# UART.net
KiCad netlist of a schematic drawn in Altium Designer
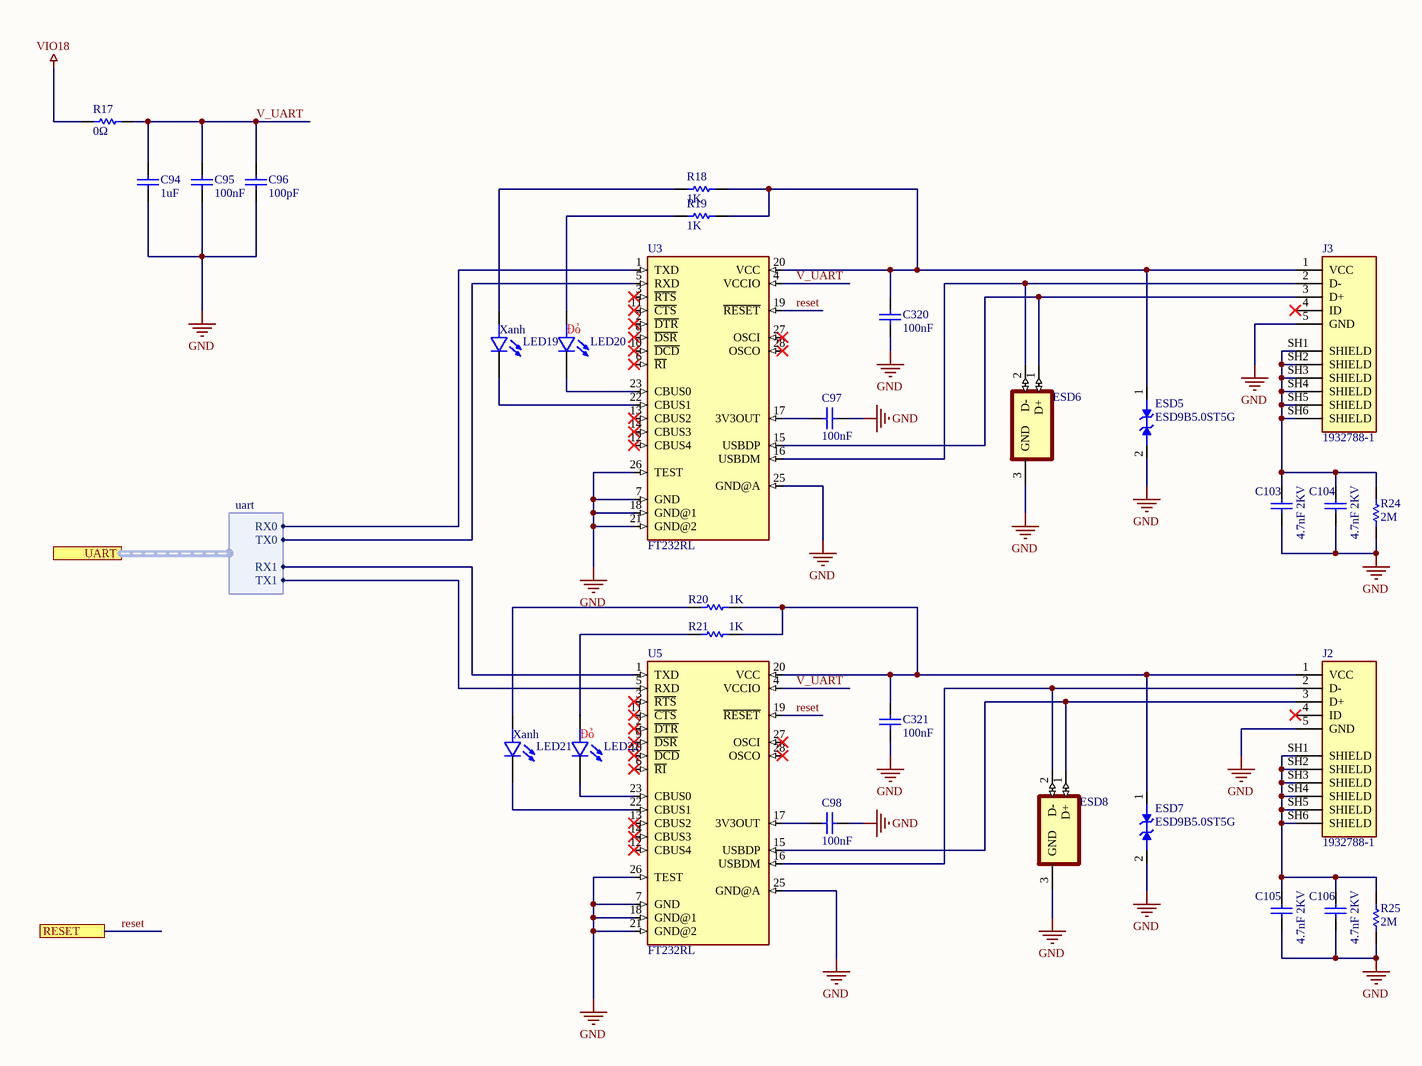
[diagram p0: UART.SchDoc]

(export (version "E")
  (design (tool "Eeschema 10.0.6"))
  (components
    (comp (ref "C94")
      (value "1uF")
      (footprint "C0805")
      (fields (field (name "Comment") "C0805"))
      (libsource (lib "kit") (part "C0805"))
    )
    (comp (ref "C95")
      (value "100nF")
      (footprint "C0603")
      (fields (field (name "Comment") "C0603"))
      (libsource (lib "kit") (part "C0603"))
    )
    (comp (ref "C96")
      (value "100pF")
      (footprint "C0402")
      (fields (field (name "Comment") "C0402"))
      (libsource (lib "kit") (part "C0402"))
    )
    (comp (ref "C97")
      (value "100nF")
      (footprint "C0603")
      (fields (field (name "Comment") "C0603"))
      (libsource (lib "kit") (part "C0603"))
    )
    (comp (ref "C98")
      (value "100nF")
      (footprint "C0603")
      (fields (field (name "Comment") "C0603"))
      (libsource (lib "kit") (part "C0603"))
    )
    (comp (ref "C103")
      (value "4.7nF 2KV")
      (footprint "C1210")
      (fields (field (name "Comment") "C1210"))
      (libsource (lib "kit") (part "C1210"))
    )
    (comp (ref "C104")
      (value "4.7nF 2KV")
      (footprint "C1210")
      (fields (field (name "Comment") "C1210"))
      (libsource (lib "kit") (part "C1210"))
    )
    (comp (ref "C105")
      (value "4.7nF 2KV")
      (footprint "C1210")
      (fields (field (name "Comment") "C1210"))
      (libsource (lib "kit") (part "C1210"))
    )
    (comp (ref "C106")
      (value "4.7nF 2KV")
      (footprint "C1210")
      (fields (field (name "Comment") "C1210"))
      (libsource (lib "kit") (part "C1210"))
    )
    (comp (ref "C320")
      (value "100nF")
      (footprint "C0603")
      (fields (field (name "Comment") "C0603"))
      (libsource (lib "kit") (part "C0603"))
    )
    (comp (ref "C321")
      (value "100nF")
      (footprint "C0603")
      (fields (field (name "Comment") "C0603"))
      (libsource (lib "kit") (part "C0603"))
    )
    (comp (ref "ESD5")
      (value "ESD9B5.0ST5G")
      (footprint "SODFL1006X40N")
      (description "Clamp Ipp Tvs Diode Surface Mount SOD-923")
      (libsource (lib "kit") (part "ESD9B5.0ST5G"))
    )
    (comp (ref "ESD6")
      (value "TPD2EUSB30DRTR")
      (footprint "SOTFL35P100X50-3N")
      (description "2-channel ESD solution for SuperSpeed USB 3.0 interface 3-SOT-9X3 -40 to 85")
      (libsource (lib "kit") (part "TPD2EUSB30DRTR"))
    )
    (comp (ref "ESD7")
      (value "ESD9B5.0ST5G")
      (footprint "SODFL1006X40N")
      (description "Clamp Ipp Tvs Diode Surface Mount SOD-923")
      (libsource (lib "kit") (part "ESD9B5.0ST5G"))
    )
    (comp (ref "ESD8")
      (value "TPD2EUSB30DRTR")
      (footprint "SOTFL35P100X50-3N")
      (description "2-channel ESD solution for SuperSpeed USB 3.0 interface 3-SOT-9X3 -40 to 85")
      (libsource (lib "kit") (part "TPD2EUSB30DRTR"))
    )
    (comp (ref "J2")
      (value "1932788-1")
      (footprint "TE_1932788-1")
      (libsource (lib "kit") (part "1932788-1"))
    )
    (comp (ref "J3")
      (value "1932788-1")
      (footprint "TE_1932788-1")
      (libsource (lib "kit") (part "1932788-1"))
    )
    (comp (ref "LED19")
      (value "LED0402")
      (footprint "LED0402")
      (description "LED SMD")
      (libsource (lib "kit") (part "LED0402"))
    )
    (comp (ref "LED20")
      (value "LED0402")
      (footprint "LED0402")
      (description "LED SMD")
      (libsource (lib "kit") (part "LED0402"))
    )
    (comp (ref "LED21")
      (value "LED0402")
      (footprint "LED0402")
      (description "LED SMD")
      (libsource (lib "kit") (part "LED0402"))
    )
    (comp (ref "LED22")
      (value "LED0402")
      (footprint "LED0402")
      (description "LED SMD")
      (libsource (lib "kit") (part "LED0402"))
    )
    (comp (ref "R17")
      (value "0Ω")
      (footprint "R0603")
      (fields (field (name "Comment") "R0603"))
      (libsource (lib "kit") (part "R0603"))
    )
    (comp (ref "R18")
      (value "1K")
      (footprint "R0603")
      (fields (field (name "Comment") "R0603"))
      (libsource (lib "kit") (part "R0603"))
    )
    (comp (ref "R19")
      (value "1K")
      (footprint "R0603")
      (fields (field (name "Comment") "R0603"))
      (libsource (lib "kit") (part "R0603"))
    )
    (comp (ref "R20")
      (value "1K")
      (footprint "R0603")
      (fields (field (name "Comment") "R0603"))
      (libsource (lib "kit") (part "R0603"))
    )
    (comp (ref "R21")
      (value "1K")
      (footprint "R0603")
      (fields (field (name "Comment") "R0603"))
      (libsource (lib "kit") (part "R0603"))
    )
    (comp (ref "R24")
      (value "2M")
      (footprint "R0603")
      (fields (field (name "Comment") "R0603"))
      (libsource (lib "kit") (part "R0603"))
    )
    (comp (ref "R25")
      (value "2M")
      (footprint "R0603")
      (fields (field (name "Comment") "R0603"))
      (libsource (lib "kit") (part "R0603"))
    )
    (comp (ref "U3") (value "FT232RL") (footprint "FT232RL") (libsource (lib "kit") (part "FT232RL")))
    (comp (ref "U5") (value "FT232RL") (footprint "FT232RL") (libsource (lib "kit") (part "FT232RL")))
  )
  (nets
    (net (code "2") (name "/RX0") (class "Default")
      (node (ref "U3") (pin "1") (pinfunction "TXD_1") (pintype "input"))
    )
    (net (code "3") (name "/RX1") (class "Default")
      (node (ref "U5") (pin "1") (pinfunction "TXD_1") (pintype "input"))
    )
    (net (code "4") (name "/TX0") (class "Default")
      (node (ref "U3") (pin "5") (pinfunction "RXD_5") (pintype "input"))
    )
    (net (code "5") (name "/TX1") (class "Default")
      (node (ref "U5") (pin "5") (pinfunction "RXD_5") (pintype "input"))
    )
    (net (code "6") (name "/V_UART") (class "Default")
      (node (ref "C94") (pin "1") (pinfunction "1_1") (pintype "passive"))
      (node (ref "C95") (pin "2") (pinfunction "2_2") (pintype "passive"))
      (node (ref "C96") (pin "2") (pinfunction "2_2") (pintype "passive"))
      (node (ref "R17") (pin "2") (pinfunction "2_2") (pintype "passive"))
      (node (ref "U3") (pin "4") (pinfunction "VCCIO_4") (pintype "input"))
      (node (ref "U5") (pin "4") (pinfunction "VCCIO_4") (pintype "input"))
    )
    (net (code "7") (name "/reset") (class "Default")
      (node (ref "U3") (pin "19") (pinfunction "~{RESET}_19") (pintype "input"))
      (node (ref "U5") (pin "19") (pinfunction "~{RESET}_19") (pintype "input"))
    )
    (net (code "9") (name "GND") (class "Default")
      (node (ref "C103") (pin "1") (pinfunction "1_1") (pintype "passive"))
      (node (ref "C104") (pin "1") (pinfunction "1_1") (pintype "passive"))
      (node (ref "C105") (pin "1") (pinfunction "1_1") (pintype "passive"))
      (node (ref "C106") (pin "1") (pinfunction "1_1") (pintype "passive"))
      (node (ref "C320") (pin "1") (pinfunction "1_1") (pintype "passive"))
      (node (ref "C321") (pin "1") (pinfunction "1_1") (pintype "passive"))
      (node (ref "C94") (pin "2") (pinfunction "2_2") (pintype "passive"))
      (node (ref "C95") (pin "1") (pinfunction "1_1") (pintype "passive"))
      (node (ref "C96") (pin "1") (pinfunction "1_1") (pintype "passive"))
      (node (ref "C97") (pin "1") (pinfunction "1_1") (pintype "passive"))
      (node (ref "C98") (pin "1") (pinfunction "1_1") (pintype "passive"))
      (node (ref "ESD5") (pin "2") (pinfunction "A1_2") (pintype "passive"))
      (node (ref "ESD6") (pin "3") (pinfunction "GND_3") (pintype "power_in"))
      (node (ref "ESD7") (pin "2") (pinfunction "A1_2") (pintype "passive"))
      (node (ref "ESD8") (pin "3") (pinfunction "GND_3") (pintype "power_in"))
      (node (ref "J2") (pin "5") (pinfunction "GND_5") (pintype "power_in"))
      (node (ref "J3") (pin "5") (pinfunction "GND_5") (pintype "power_in"))
      (node (ref "R24") (pin "2") (pinfunction "2_2") (pintype "passive"))
      (node (ref "R25") (pin "2") (pinfunction "2_2") (pintype "passive"))
      (node (ref "U3") (pin "18") (pinfunction "GND@1_18") (pintype "input"))
      (node (ref "U3") (pin "21") (pinfunction "GND@2_21") (pintype "input"))
      (node (ref "U3") (pin "25") (pinfunction "GND@A_25") (pintype "input"))
      (node (ref "U3") (pin "26") (pinfunction "TEST_26") (pintype "input"))
      (node (ref "U3") (pin "7") (pinfunction "GND_7") (pintype "input"))
      (node (ref "U5") (pin "18") (pinfunction "GND@1_18") (pintype "input"))
      (node (ref "U5") (pin "21") (pinfunction "GND@2_21") (pintype "input"))
      (node (ref "U5") (pin "25") (pinfunction "GND@A_25") (pintype "input"))
      (node (ref "U5") (pin "26") (pinfunction "TEST_26") (pintype "input"))
      (node (ref "U5") (pin "7") (pinfunction "GND_7") (pintype "input"))
    )
    (net (code "10") (name "Net-(C103-Pad2)") (class "Default")
      (node (ref "C103") (pin "2") (pinfunction "2_2") (pintype "passive"))
      (node (ref "C104") (pin "2") (pinfunction "2_2") (pintype "passive"))
      (node (ref "J3") (pin "SH1") (pinfunction "SHIELD_SH1") (pintype "passive"))
      (node (ref "J3") (pin "SH2") (pinfunction "SHIELD_SH2") (pintype "passive"))
      (node (ref "J3") (pin "SH3") (pinfunction "SHIELD_SH3") (pintype "passive"))
      (node (ref "J3") (pin "SH4") (pinfunction "SHIELD_SH4") (pintype "passive"))
      (node (ref "J3") (pin "SH5") (pinfunction "SHIELD_SH5") (pintype "passive"))
      (node (ref "J3") (pin "SH6") (pinfunction "SHIELD_SH6") (pintype "passive"))
      (node (ref "R24") (pin "1") (pinfunction "1_1") (pintype "passive"))
    )
    (net (code "11") (name "Net-(C105-Pad2)") (class "Default")
      (node (ref "C105") (pin "2") (pinfunction "2_2") (pintype "passive"))
      (node (ref "C106") (pin "2") (pinfunction "2_2") (pintype "passive"))
      (node (ref "J2") (pin "SH1") (pinfunction "SHIELD_SH1") (pintype "passive"))
      (node (ref "J2") (pin "SH2") (pinfunction "SHIELD_SH2") (pintype "passive"))
      (node (ref "J2") (pin "SH3") (pinfunction "SHIELD_SH3") (pintype "passive"))
      (node (ref "J2") (pin "SH4") (pinfunction "SHIELD_SH4") (pintype "passive"))
      (node (ref "J2") (pin "SH5") (pinfunction "SHIELD_SH5") (pintype "passive"))
      (node (ref "J2") (pin "SH6") (pinfunction "SHIELD_SH6") (pintype "passive"))
      (node (ref "R25") (pin "1") (pinfunction "1_1") (pintype "passive"))
    )
    (net (code "12") (name "Net-(ESD5-A)") (class "Default")
      (node (ref "C320") (pin "2") (pinfunction "2_2") (pintype "passive"))
      (node (ref "ESD5") (pin "1") (pinfunction "A_1") (pintype "passive"))
      (node (ref "J3") (pin "1") (pinfunction "VCC_1") (pintype "power_in"))
      (node (ref "R18") (pin "2") (pinfunction "2_2") (pintype "passive"))
      (node (ref "R19") (pin "2") (pinfunction "2_2") (pintype "passive"))
      (node (ref "U3") (pin "20") (pinfunction "VCC_20") (pintype "input"))
    )
    (net (code "13") (name "Net-(ESD6-D+)") (class "Default")
      (node (ref "ESD6") (pin "1") (pinfunction "D+_1") (pintype "bidirectional"))
      (node (ref "J3") (pin "3") (pinfunction "D+_3") (pintype "passive"))
      (node (ref "U3") (pin "15") (pinfunction "USBDP_15") (pintype "input"))
    )
    (net (code "14") (name "Net-(ESD6-D-)") (class "Default")
      (node (ref "ESD6") (pin "2") (pinfunction "D-_2") (pintype "bidirectional"))
      (node (ref "J3") (pin "2") (pinfunction "D-_2") (pintype "passive"))
      (node (ref "U3") (pin "16") (pinfunction "USBDM_16") (pintype "input"))
    )
    (net (code "15") (name "Net-(ESD7-A)") (class "Default")
      (node (ref "C321") (pin "2") (pinfunction "2_2") (pintype "passive"))
      (node (ref "ESD7") (pin "1") (pinfunction "A_1") (pintype "passive"))
      (node (ref "J2") (pin "1") (pinfunction "VCC_1") (pintype "power_in"))
      (node (ref "R20") (pin "2") (pinfunction "2_2") (pintype "passive"))
      (node (ref "R21") (pin "2") (pinfunction "2_2") (pintype "passive"))
      (node (ref "U5") (pin "20") (pinfunction "VCC_20") (pintype "input"))
    )
    (net (code "16") (name "Net-(ESD8-D+)") (class "Default")
      (node (ref "ESD8") (pin "1") (pinfunction "D+_1") (pintype "bidirectional"))
      (node (ref "J2") (pin "3") (pinfunction "D+_3") (pintype "passive"))
      (node (ref "U5") (pin "15") (pinfunction "USBDP_15") (pintype "input"))
    )
    (net (code "17") (name "Net-(ESD8-D-)") (class "Default")
      (node (ref "ESD8") (pin "2") (pinfunction "D-_2") (pintype "bidirectional"))
      (node (ref "J2") (pin "2") (pinfunction "D-_2") (pintype "passive"))
      (node (ref "U5") (pin "16") (pinfunction "USBDM_16") (pintype "input"))
    )
    (net (code "18") (name "Net-(LED19-PadA)") (class "Default")
      (node (ref "LED19") (pin "A") (pinfunction "A_A") (pintype "passive"))
      (node (ref "R18") (pin "1") (pinfunction "1_1") (pintype "passive"))
    )
    (net (code "19") (name "Net-(LED20-PadA)") (class "Default")
      (node (ref "LED20") (pin "A") (pinfunction "A_A") (pintype "passive"))
      (node (ref "R19") (pin "1") (pinfunction "1_1") (pintype "passive"))
    )
    (net (code "20") (name "Net-(LED21-PadA)") (class "Default")
      (node (ref "LED21") (pin "A") (pinfunction "A_A") (pintype "passive"))
      (node (ref "R20") (pin "1") (pinfunction "1_1") (pintype "passive"))
    )
    (net (code "21") (name "Net-(LED22-PadA)") (class "Default")
      (node (ref "LED22") (pin "A") (pinfunction "A_A") (pintype "passive"))
      (node (ref "R21") (pin "1") (pinfunction "1_1") (pintype "passive"))
    )
    (net (code "22") (name "Net-(U3-3V3OUT)") (class "Default")
      (node (ref "C97") (pin "2") (pinfunction "2_2") (pintype "passive"))
      (node (ref "U3") (pin "17") (pinfunction "3V3OUT_17") (pintype "input"))
    )
    (net (code "23") (name "Net-(U3-CBUS0)") (class "Default")
      (node (ref "LED20") (pin "C") (pinfunction "C_C") (pintype "passive"))
      (node (ref "U3") (pin "23") (pinfunction "CBUS0_23") (pintype "input"))
    )
    (net (code "24") (name "Net-(U3-CBUS1)") (class "Default")
      (node (ref "LED19") (pin "C") (pinfunction "C_C") (pintype "passive"))
      (node (ref "U3") (pin "22") (pinfunction "CBUS1_22") (pintype "input"))
    )
    (net (code "25") (name "Net-(U5-3V3OUT)") (class "Default")
      (node (ref "C98") (pin "2") (pinfunction "2_2") (pintype "passive"))
      (node (ref "U5") (pin "17") (pinfunction "3V3OUT_17") (pintype "input"))
    )
    (net (code "26") (name "Net-(U5-CBUS0)") (class "Default")
      (node (ref "LED22") (pin "C") (pinfunction "C_C") (pintype "passive"))
      (node (ref "U5") (pin "23") (pinfunction "CBUS0_23") (pintype "input"))
    )
    (net (code "27") (name "Net-(U5-CBUS1)") (class "Default")
      (node (ref "LED21") (pin "C") (pinfunction "C_C") (pintype "passive"))
      (node (ref "U5") (pin "22") (pinfunction "CBUS1_22") (pintype "input"))
    )
    (net (code "28") (name "VIO18") (class "Default")
      (node (ref "R17") (pin "1") (pinfunction "1_1") (pintype "passive"))
    )
    (net (code "29") (name "unconnected-(J2-ID-Pad4)") (class "Default")
      (node (ref "J2") (pin "4") (pinfunction "ID_4") (pintype "passive+no_connect"))
    )
    (net (code "30") (name "unconnected-(J3-ID-Pad4)") (class "Default")
      (node (ref "J3") (pin "4") (pinfunction "ID_4") (pintype "passive+no_connect"))
    )
    (net (code "31") (name "unconnected-(U3-CBUS2-Pad13)") (class "Default")
      (node (ref "U3") (pin "13") (pinfunction "CBUS2_13") (pintype "input+no_connect"))
    )
    (net (code "32") (name "unconnected-(U3-CBUS3-Pad14)") (class "Default")
      (node (ref "U3") (pin "14") (pinfunction "CBUS3_14") (pintype "input+no_connect"))
    )
    (net (code "33") (name "unconnected-(U3-CBUS4-Pad12)") (class "Default")
      (node (ref "U3") (pin "12") (pinfunction "CBUS4_12") (pintype "input+no_connect"))
    )
    (net (code "34") (name "unconnected-(U3-OSCI-Pad27)") (class "Default")
      (node (ref "U3") (pin "27") (pinfunction "OSCI_27") (pintype "input+no_connect"))
    )
    (net (code "35") (name "unconnected-(U3-OSCO-Pad28)") (class "Default")
      (node (ref "U3") (pin "28") (pinfunction "OSCO_28") (pintype "input+no_connect"))
    )
    (net (code "36") (name "unconnected-(U3-~{CTS}-Pad11)") (class "Default")
      (node (ref "U3") (pin "11") (pinfunction "~{CTS}_11") (pintype "input+no_connect"))
    )
    (net (code "37") (name "unconnected-(U3-~{DCD}-Pad10)") (class "Default")
      (node (ref "U3") (pin "10") (pinfunction "~{DCD}_10") (pintype "input+no_connect"))
    )
    (net (code "38") (name "unconnected-(U3-~{DSR}-Pad9)") (class "Default")
      (node (ref "U3") (pin "9") (pinfunction "~{DSR}_9") (pintype "input+no_connect"))
    )
    (net (code "39") (name "unconnected-(U3-~{DTR}-Pad2)") (class "Default")
      (node (ref "U3") (pin "2") (pinfunction "~{DTR}_2") (pintype "input+no_connect"))
    )
    (net (code "40") (name "unconnected-(U3-~{RI}-Pad6)") (class "Default")
      (node (ref "U3") (pin "6") (pinfunction "~{RI}_6") (pintype "input+no_connect"))
    )
    (net (code "41") (name "unconnected-(U3-~{RTS}-Pad3)") (class "Default")
      (node (ref "U3") (pin "3") (pinfunction "~{RTS}_3") (pintype "input+no_connect"))
    )
    (net (code "42") (name "unconnected-(U5-CBUS2-Pad13)") (class "Default")
      (node (ref "U5") (pin "13") (pinfunction "CBUS2_13") (pintype "input+no_connect"))
    )
    (net (code "43") (name "unconnected-(U5-CBUS3-Pad14)") (class "Default")
      (node (ref "U5") (pin "14") (pinfunction "CBUS3_14") (pintype "input+no_connect"))
    )
    (net (code "44") (name "unconnected-(U5-CBUS4-Pad12)") (class "Default")
      (node (ref "U5") (pin "12") (pinfunction "CBUS4_12") (pintype "input+no_connect"))
    )
    (net (code "45") (name "unconnected-(U5-OSCI-Pad27)") (class "Default")
      (node (ref "U5") (pin "27") (pinfunction "OSCI_27") (pintype "input+no_connect"))
    )
    (net (code "46") (name "unconnected-(U5-OSCO-Pad28)") (class "Default")
      (node (ref "U5") (pin "28") (pinfunction "OSCO_28") (pintype "input+no_connect"))
    )
    (net (code "47") (name "unconnected-(U5-~{CTS}-Pad11)") (class "Default")
      (node (ref "U5") (pin "11") (pinfunction "~{CTS}_11") (pintype "input+no_connect"))
    )
    (net (code "48") (name "unconnected-(U5-~{DCD}-Pad10)") (class "Default")
      (node (ref "U5") (pin "10") (pinfunction "~{DCD}_10") (pintype "input+no_connect"))
    )
    (net (code "49") (name "unconnected-(U5-~{DSR}-Pad9)") (class "Default")
      (node (ref "U5") (pin "9") (pinfunction "~{DSR}_9") (pintype "input+no_connect"))
    )
    (net (code "50") (name "unconnected-(U5-~{DTR}-Pad2)") (class "Default")
      (node (ref "U5") (pin "2") (pinfunction "~{DTR}_2") (pintype "input+no_connect"))
    )
    (net (code "51") (name "unconnected-(U5-~{RI}-Pad6)") (class "Default")
      (node (ref "U5") (pin "6") (pinfunction "~{RI}_6") (pintype "input+no_connect"))
    )
    (net (code "52") (name "unconnected-(U5-~{RTS}-Pad3)") (class "Default")
      (node (ref "U5") (pin "3") (pinfunction "~{RTS}_3") (pintype "input+no_connect"))
    )
  )
)
